# 1-Schematic_RGB_project.net
KiCad netlist of a schematic drawn in EasyEDA
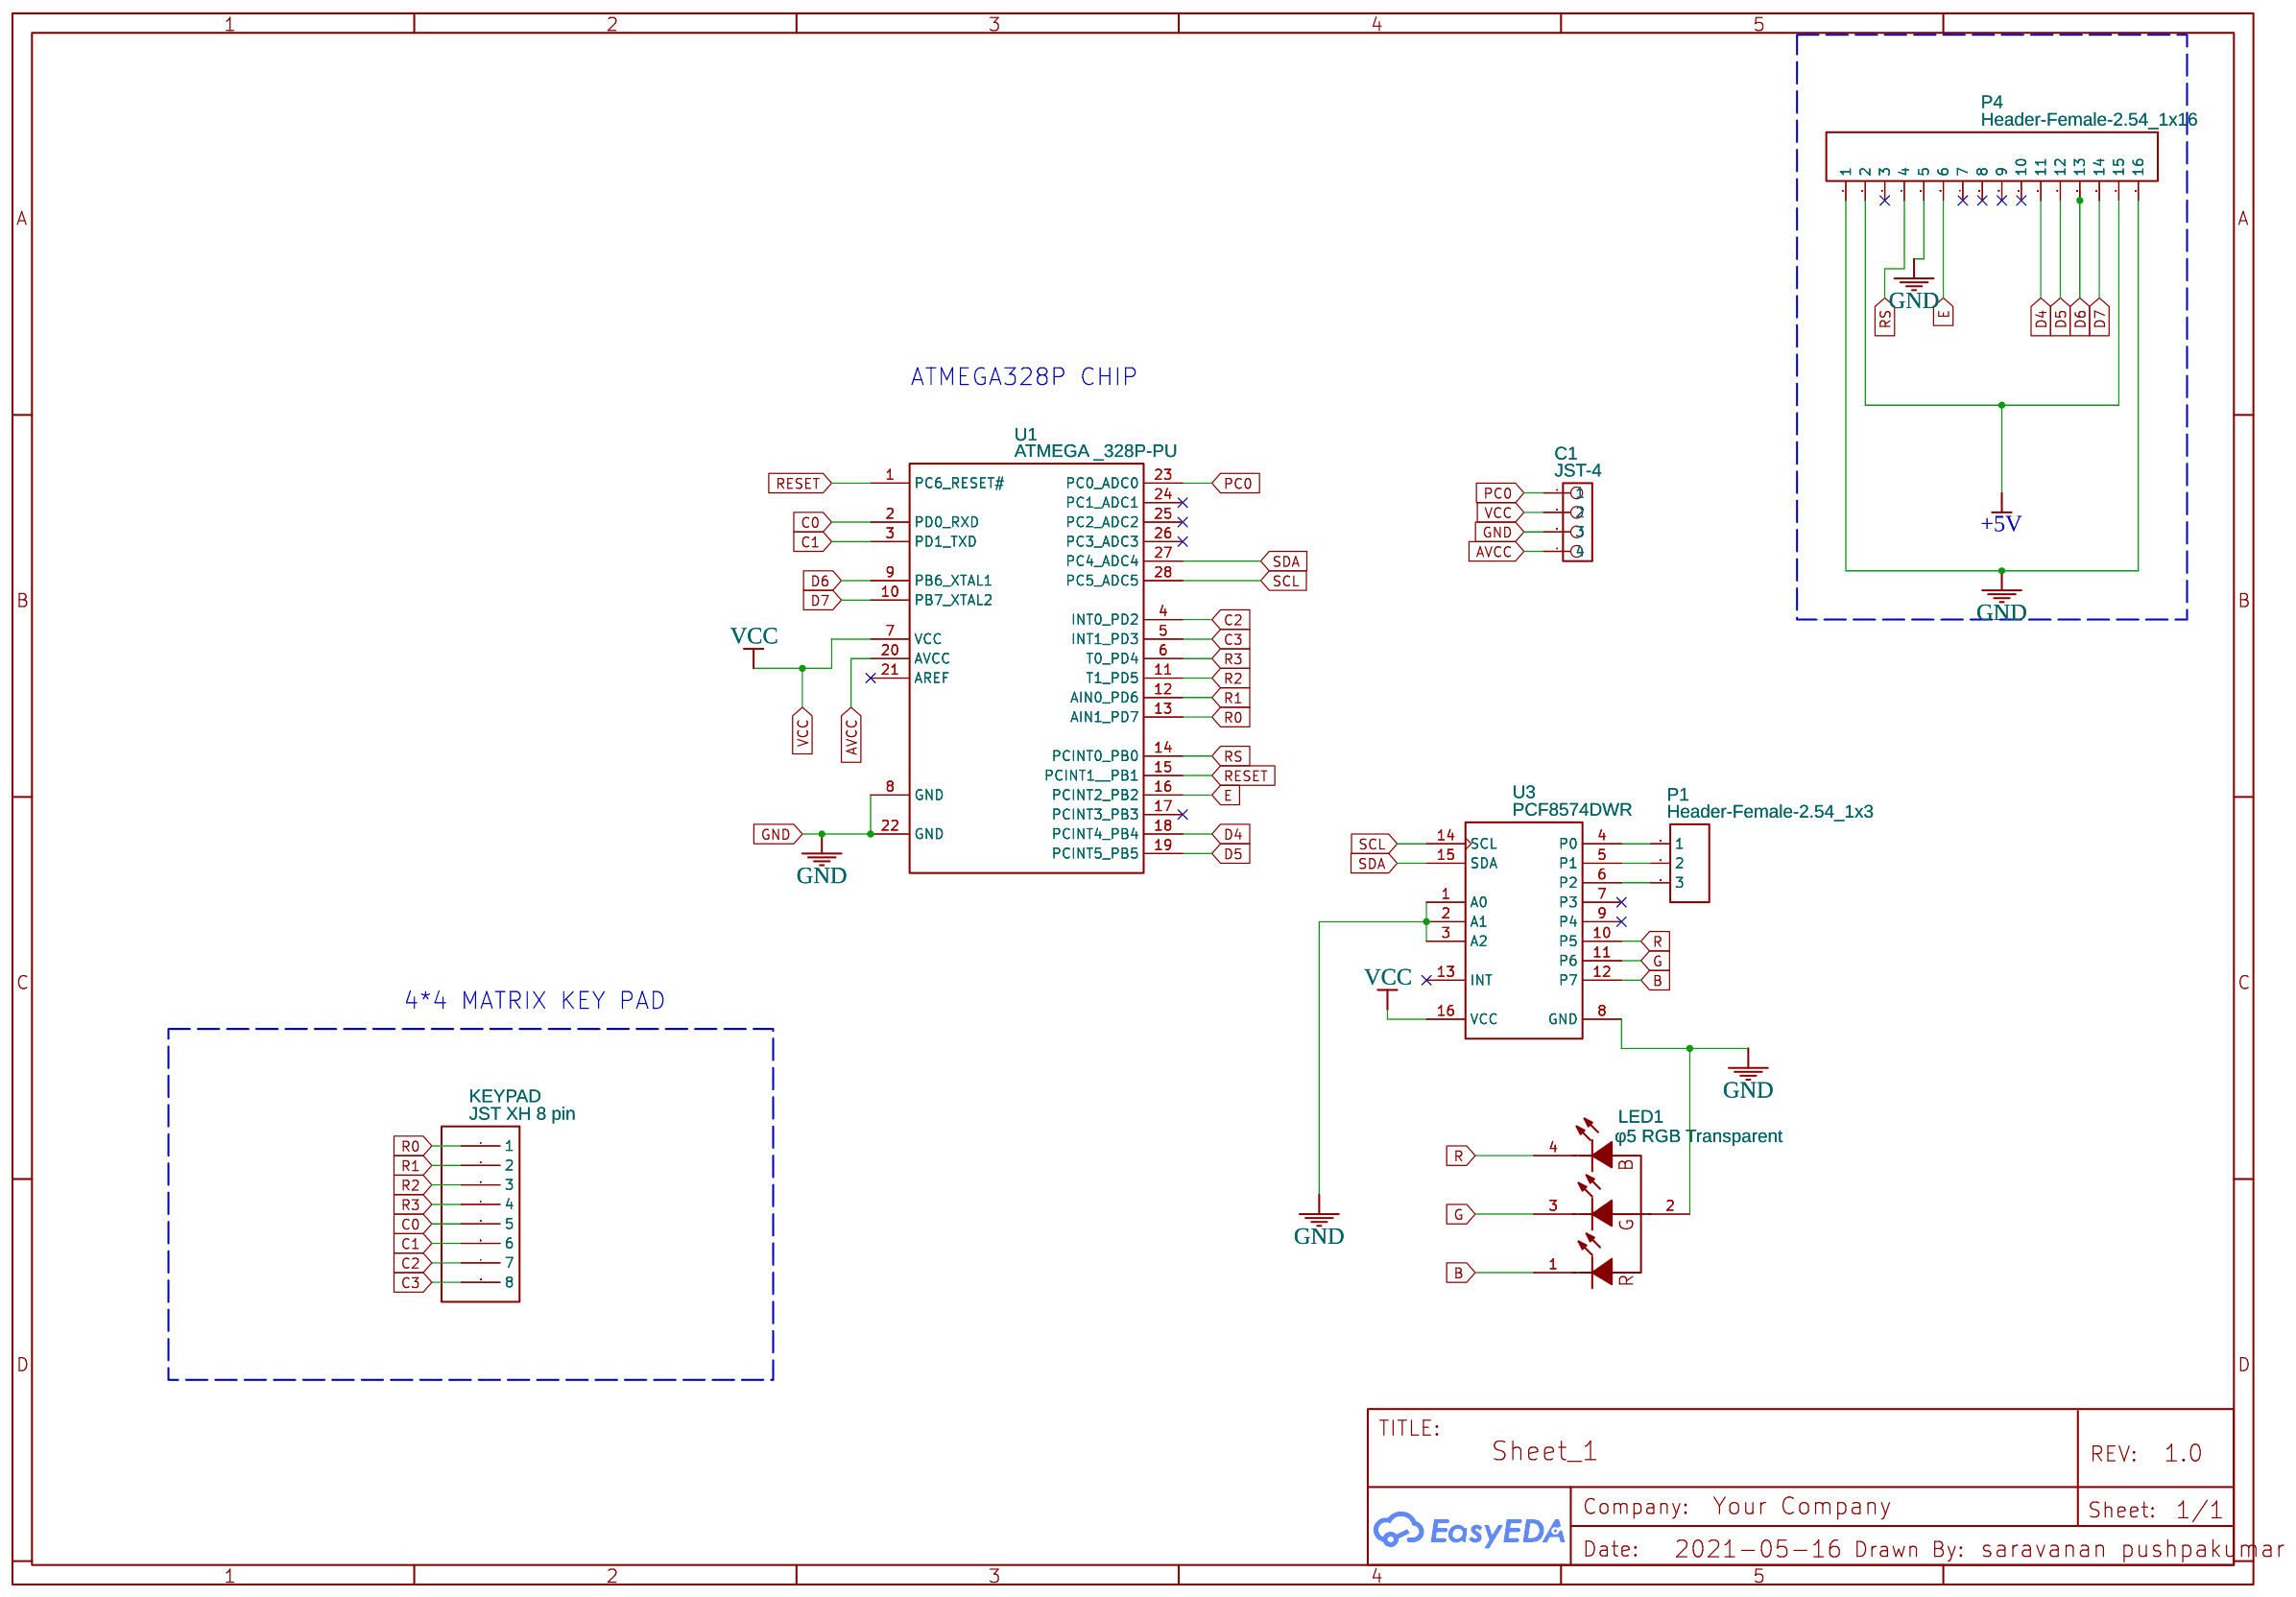
[diagram p0: schematic sheet]

(export (version "E")
  (design (tool "Eeschema 10.0.6"))
  (components
    (comp (ref "C1")
      (value "JST-4")
      (fields (field (name "BOM_Manufacturer Part") "XH-4A"))
      (libsource (lib "") (part "JST-4"))
    )
    (comp (ref "KEYPAD")
      (value "JST XH 8 pin")
      (fields (field (name "BOM_Supplier Part") "undefined"))
      (libsource (lib "") (part "JST XH 8 pin"))
    )
    (comp (ref "LED1")
      (value "φ5 RGB Transparent")
      (fields
        (field (name "BOM_Manufacturer Part") "φ5 RGB Transparent LED")
        (field (name "BOM_Supplier Part") "C32985")
      )
      (libsource (lib "") (part "φ5 RGB Transparent"))
    )
    (comp (ref "P1")
      (value "Header-Female-2.54_1x3")
      (fields (field (name "BOM_Supplier Part") "C146243"))
      (libsource (lib "") (part "Header-Female-2.54_1x3"))
    )
    (comp (ref "P4")
      (value "Header-Female-2.54_1x16")
      (fields
        (field (name "BOM_Manufacturer Part") "Female header1*16P pitch 2.54mm")
        (field (name "BOM_Supplier Part") "C66987")
      )
      (libsource (lib "") (part "Header-Female-2.54_1x16"))
    )
    (comp (ref "U1")
      (value "ATMEGA _328P-PU")
      (fields
        (field (name "BOM_Manufacturer Part") "ATMEGA328P-PU")
        (field (name "BOM_Supplier Part") "C33901")
      )
      (libsource (lib "") (part "ATMEGA _328P-PU"))
    )
    (comp (ref "U3") (value "PCF8574DWR") (libsource (lib "") (part "PCF8574DWR")))
  )
  (nets
    (net (code "1") (name "+5V") (class "Default")
      (node (ref "P4") (pin "15") (pinfunction "15_15") (pintype "input"))
      (node (ref "P4") (pin "2") (pinfunction "2_2") (pintype "input"))
    )
    (net (code "2") (name "AVCC") (class "Default")
      (node (ref "C1") (pin "4") (pinfunction "4_4") (pintype "unspecified"))
      (node (ref "U1") (pin "20") (pinfunction "AVCC_20") (pintype "passive"))
    )
    (net (code "3") (name "B") (class "Default")
      (node (ref "LED1") (pin "1") (pinfunction "KR_1") (pintype "unspecified"))
      (node (ref "U3") (pin "12") (pinfunction "P7_12") (pintype "bidirectional"))
    )
    (net (code "4") (name "C0") (class "Default")
      (node (ref "KEYPAD") (pin "5") (pinfunction "5_5") (pintype "unspecified"))
      (node (ref "U1") (pin "2") (pinfunction "PD0_RXD_2") (pintype "bidirectional"))
    )
    (net (code "5") (name "C1") (class "Default")
      (node (ref "KEYPAD") (pin "6") (pinfunction "6_6") (pintype "unspecified"))
      (node (ref "U1") (pin "3") (pinfunction "PD1_TXD_3") (pintype "bidirectional"))
    )
    (net (code "6") (name "C2") (class "Default")
      (node (ref "KEYPAD") (pin "7") (pinfunction "7_7") (pintype "unspecified"))
      (node (ref "U1") (pin "4") (pinfunction "INT0_PD2_4") (pintype "bidirectional"))
    )
    (net (code "7") (name "C3") (class "Default")
      (node (ref "KEYPAD") (pin "8") (pinfunction "8_8") (pintype "unspecified"))
      (node (ref "U1") (pin "5") (pinfunction "INT1_PD3_5") (pintype "bidirectional"))
    )
    (net (code "8") (name "D4") (class "Default")
      (node (ref "P4") (pin "11") (pinfunction "11_11") (pintype "input"))
      (node (ref "U1") (pin "18") (pinfunction "PCINT4_PB4_18") (pintype "bidirectional"))
    )
    (net (code "9") (name "D5") (class "Default")
      (node (ref "P4") (pin "12") (pinfunction "12_12") (pintype "input"))
      (node (ref "U1") (pin "19") (pinfunction "PCINT5_PB5_19") (pintype "bidirectional"))
    )
    (net (code "10") (name "D6") (class "Default")
      (node (ref "P4") (pin "13") (pinfunction "13_13") (pintype "input"))
      (node (ref "U1") (pin "9") (pinfunction "PB6_XTAL1_9") (pintype "bidirectional"))
    )
    (net (code "11") (name "D7") (class "Default")
      (node (ref "P4") (pin "14") (pinfunction "14_14") (pintype "input"))
      (node (ref "U1") (pin "10") (pinfunction "PB7_XTAL2_10") (pintype "bidirectional"))
    )
    (net (code "12") (name "E") (class "Default")
      (node (ref "P4") (pin "6") (pinfunction "6_6") (pintype "input"))
      (node (ref "U1") (pin "16") (pinfunction "PCINT2_PB2_16") (pintype "bidirectional"))
    )
    (net (code "13") (name "G") (class "Default")
      (node (ref "LED1") (pin "3") (pinfunction "KG_3") (pintype "unspecified"))
      (node (ref "U3") (pin "11") (pinfunction "P6_11") (pintype "bidirectional"))
    )
    (net (code "14") (name "GND") (class "Default")
      (node (ref "C1") (pin "3") (pinfunction "3_3") (pintype "unspecified"))
      (node (ref "LED1") (pin "2") (pinfunction "CA_2") (pintype "unspecified"))
      (node (ref "P4") (pin "1") (pinfunction "1_1") (pintype "input"))
      (node (ref "P4") (pin "16") (pinfunction "16_16") (pintype "input"))
      (node (ref "P4") (pin "5") (pinfunction "5_5") (pintype "input"))
      (node (ref "U1") (pin "22") (pinfunction "GND_22") (pintype "passive"))
      (node (ref "U1") (pin "8") (pinfunction "GND_8") (pintype "passive"))
      (node (ref "U3") (pin "1") (pinfunction "A0_1") (pintype "unspecified"))
      (node (ref "U3") (pin "2") (pinfunction "A1_2") (pintype "unspecified"))
      (node (ref "U3") (pin "3") (pinfunction "A2_3") (pintype "unspecified"))
      (node (ref "U3") (pin "8") (pinfunction "GND_8") (pintype "passive"))
    )
    (net (code "15") (name "Net-(U3-P0)") (class "Default")
      (node (ref "P1") (pin "1") (pinfunction "1_1") (pintype "input"))
      (node (ref "U3") (pin "4") (pinfunction "P0_4") (pintype "bidirectional"))
    )
    (net (code "16") (name "Net-(U3-P1)") (class "Default")
      (node (ref "P1") (pin "2") (pinfunction "2_2") (pintype "input"))
      (node (ref "U3") (pin "5") (pinfunction "P1_5") (pintype "bidirectional"))
    )
    (net (code "17") (name "Net-(U3-P2)") (class "Default")
      (node (ref "P1") (pin "3") (pinfunction "3_3") (pintype "input"))
      (node (ref "U3") (pin "6") (pinfunction "P2_6") (pintype "bidirectional"))
    )
    (net (code "18") (name "PC0") (class "Default")
      (node (ref "C1") (pin "1") (pinfunction "1_1") (pintype "unspecified"))
      (node (ref "U1") (pin "23") (pinfunction "PC0_ADC0_23") (pintype "bidirectional"))
    )
    (net (code "19") (name "R") (class "Default")
      (node (ref "LED1") (pin "4") (pinfunction "KB_4") (pintype "unspecified"))
      (node (ref "U3") (pin "10") (pinfunction "P5_10") (pintype "bidirectional"))
    )
    (net (code "20") (name "R0") (class "Default")
      (node (ref "KEYPAD") (pin "1") (pinfunction "1_1") (pintype "unspecified"))
      (node (ref "U1") (pin "13") (pinfunction "AIN1_PD7_13") (pintype "bidirectional"))
    )
    (net (code "21") (name "R1") (class "Default")
      (node (ref "KEYPAD") (pin "2") (pinfunction "2_2") (pintype "unspecified"))
      (node (ref "U1") (pin "12") (pinfunction "AIN0_PD6_12") (pintype "bidirectional"))
    )
    (net (code "22") (name "R2") (class "Default")
      (node (ref "KEYPAD") (pin "3") (pinfunction "3_3") (pintype "unspecified"))
      (node (ref "U1") (pin "11") (pinfunction "T1_PD5_11") (pintype "bidirectional"))
    )
    (net (code "23") (name "R3") (class "Default")
      (node (ref "KEYPAD") (pin "4") (pinfunction "4_4") (pintype "unspecified"))
      (node (ref "U1") (pin "6") (pinfunction "T0_PD4_6") (pintype "bidirectional"))
    )
    (net (code "24") (name "RESET") (class "Default")
      (node (ref "U1") (pin "1") (pinfunction "PC6_RESET#_1") (pintype "bidirectional"))
      (node (ref "U1") (pin "15") (pinfunction "PCINT1__PB1_15") (pintype "bidirectional"))
    )
    (net (code "25") (name "RS") (class "Default")
      (node (ref "P4") (pin "4") (pinfunction "4_4") (pintype "input"))
      (node (ref "U1") (pin "14") (pinfunction "PCINT0_PB0_14") (pintype "bidirectional"))
    )
    (net (code "26") (name "SCL") (class "Default")
      (node (ref "U1") (pin "28") (pinfunction "PC5_ADC5_28") (pintype "bidirectional"))
      (node (ref "U3") (pin "14") (pinfunction "SCL_14") (pintype "unspecified"))
    )
    (net (code "27") (name "SDA") (class "Default")
      (node (ref "U1") (pin "27") (pinfunction "PC4_ADC4_27") (pintype "bidirectional"))
      (node (ref "U3") (pin "15") (pinfunction "SDA_15") (pintype "bidirectional"))
    )
    (net (code "28") (name "VCC") (class "Default")
      (node (ref "C1") (pin "2") (pinfunction "2_2") (pintype "unspecified"))
      (node (ref "U1") (pin "7") (pinfunction "VCC_7") (pintype "passive"))
      (node (ref "U3") (pin "16") (pinfunction "VCC_16") (pintype "passive"))
    )
    (net (code "29") (name "unconnected-(P4-Pad3)") (class "Default")
      (node (ref "P4") (pin "3") (pinfunction "3_3") (pintype "input+no_connect"))
    )
    (net (code "30") (name "unconnected-(P4-Pad7)") (class "Default")
      (node (ref "P4") (pin "7") (pinfunction "7_7") (pintype "input+no_connect"))
    )
    (net (code "31") (name "unconnected-(P4-Pad8)") (class "Default")
      (node (ref "P4") (pin "8") (pinfunction "8_8") (pintype "input+no_connect"))
    )
    (net (code "32") (name "unconnected-(P4-Pad9)") (class "Default")
      (node (ref "P4") (pin "9") (pinfunction "9_9") (pintype "input+no_connect"))
    )
    (net (code "33") (name "unconnected-(P4-Pad10)") (class "Default")
      (node (ref "P4") (pin "10") (pinfunction "10_10") (pintype "input+no_connect"))
    )
    (net (code "34") (name "unconnected-(U1-AREF-Pad21)") (class "Default")
      (node (ref "U1") (pin "21") (pinfunction "AREF_21") (pintype "passive+no_connect"))
    )
    (net (code "35") (name "unconnected-(U1-PC1_ADC1-Pad24)") (class "Default")
      (node (ref "U1") (pin "24") (pinfunction "PC1_ADC1_24") (pintype "bidirectional+no_connect"))
    )
    (net (code "36") (name "unconnected-(U1-PC2_ADC2-Pad25)") (class "Default")
      (node (ref "U1") (pin "25") (pinfunction "PC2_ADC2_25") (pintype "bidirectional+no_connect"))
    )
    (net (code "37") (name "unconnected-(U1-PC3_ADC3-Pad26)") (class "Default")
      (node (ref "U1") (pin "26") (pinfunction "PC3_ADC3_26") (pintype "bidirectional+no_connect"))
    )
    (net (code "38") (name "unconnected-(U1-PCINT3_PB3-Pad17)") (class "Default")
      (node (ref "U1") (pin "17") (pinfunction "PCINT3_PB3_17") (pintype "bidirectional+no_connect"))
    )
    (net (code "39") (name "unconnected-(U3-INT-Pad13)") (class "Default")
      (node (ref "U3") (pin "13") (pinfunction "INT_13") (pintype "unspecified+no_connect"))
    )
    (net (code "40") (name "unconnected-(U3-P3-Pad7)") (class "Default")
      (node (ref "U3") (pin "7") (pinfunction "P3_7") (pintype "bidirectional+no_connect"))
    )
    (net (code "41") (name "unconnected-(U3-P4-Pad9)") (class "Default")
      (node (ref "U3") (pin "9") (pinfunction "P4_9") (pintype "bidirectional+no_connect"))
    )
  )
)
